# M783new.net
KiCad netlist of a schematic drawn in EAGLE
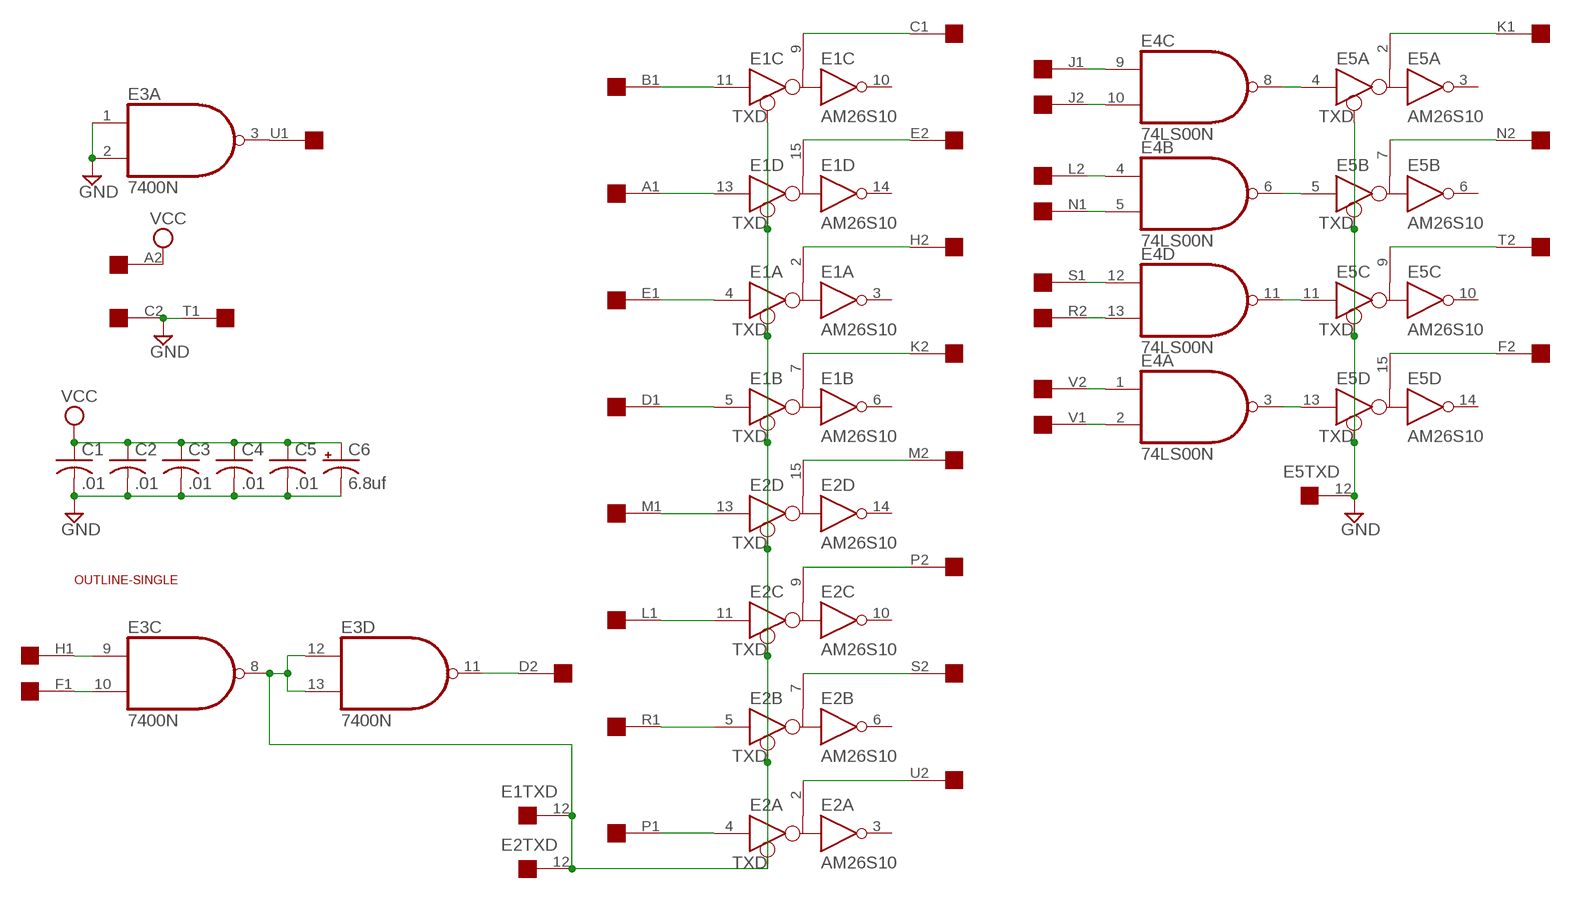
[diagram p0: schematic, sheet 1]

(export (version "E")
  (design (tool "Eeschema 10.0.6"))
  (components
    (comp (ref "C1")
      (value ".01")
      (footprint "eagle-import:C050-025X075")
      (libsource (lib "eagle-import") (part "C-US050-025X075"))
    )
    (comp (ref "C2")
      (value ".01")
      (footprint "eagle-import:C050-025X075")
      (libsource (lib "eagle-import") (part "C-US050-025X075"))
    )
    (comp (ref "C3")
      (value ".01")
      (footprint "eagle-import:C050-025X075")
      (libsource (lib "eagle-import") (part "C-US050-025X075"))
    )
    (comp (ref "C4")
      (value ".01")
      (footprint "eagle-import:C050-025X075")
      (libsource (lib "eagle-import") (part "C-US050-025X075"))
    )
    (comp (ref "C5")
      (value ".01")
      (footprint "eagle-import:C050-025X075")
      (libsource (lib "eagle-import") (part "C-US050-025X075"))
    )
    (comp (ref "C6")
      (value "6.8uf")
      (footprint "eagle-import:E15-5")
      (libsource (lib "eagle-import") (part "CPOL-USE15-5AXIAL"))
    )
    (comp (ref "E1")
      (value "AM26S10")
      (footprint "eagle-import:DIL16")
      (libsource (lib "eagle-import") (part "AM26S10"))
    )
    (comp (ref "E2")
      (value "AM26S10")
      (footprint "eagle-import:DIL16")
      (libsource (lib "eagle-import") (part "AM26S10"))
    )
    (comp (ref "E3")
      (value "7400N")
      (footprint "eagle-import:DIL14")
      (libsource (lib "eagle-import") (part "7400N"))
    )
    (comp (ref "E4")
      (value "74LS00N")
      (footprint "eagle-import:DIL14")
      (libsource (lib "eagle-import") (part "7400NLS"))
    )
    (comp (ref "E5")
      (value "AM26S10")
      (footprint "eagle-import:DIL16")
      (libsource (lib "eagle-import") (part "AM26S10"))
    )
    (comp (ref "U$1")
      (value "SINGLE")
      (footprint "eagle-import:EDGE-CON2")
      (libsource (lib "eagle-import") (part "SINGLE"))
    )
    (comp (ref "U$2")
      (value "OUTLINE-SINGLE")
      (footprint "eagle-import:SINGLE")
      (libsource (lib "eagle-import") (part "OUTLINE-SINGLE"))
    )
  )
  (nets
    (net (code "1") (name "GND") (class "Default")
      (node (ref "C1") (pin "2") (pinfunction "2_2") (pintype "passive"))
      (node (ref "C2") (pin "2") (pinfunction "2_2") (pintype "passive"))
      (node (ref "C3") (pin "2") (pinfunction "2_2") (pintype "passive"))
      (node (ref "C4") (pin "2") (pinfunction "2_2") (pintype "passive"))
      (node (ref "C5") (pin "2") (pinfunction "2_2") (pintype "passive"))
      (node (ref "C6") (pin "-") (pinfunction "-_-") (pintype "passive"))
      (node (ref "E3") (pin "1") (pinfunction "I0_1") (pintype "input"))
      (node (ref "E3") (pin "2") (pinfunction "I1_2") (pintype "input"))
      (node (ref "E5") (pin "12") (pinfunction "TXD_12") (pintype "input"))
      (node (ref "U$1") (pin "C2") (pinfunction "1_C2") (pintype "bidirectional"))
      (node (ref "U$1") (pin "T1") (pinfunction "1_T1") (pintype "bidirectional"))
    )
    (net (code "2") (name "Net-(E1A-B)") (class "Default")
      (node (ref "E1") (pin "2") (pinfunction "B_2") (pintype "bidirectional"))
      (node (ref "U$1") (pin "H2") (pinfunction "1_H2") (pintype "bidirectional"))
    )
    (net (code "3") (name "Net-(E1A-D)") (class "Default")
      (node (ref "E1") (pin "4") (pinfunction "D_4") (pintype "input"))
      (node (ref "U$1") (pin "E1") (pinfunction "1_E1") (pintype "bidirectional"))
    )
    (net (code "4") (name "Net-(E1B-B)") (class "Default")
      (node (ref "E1") (pin "7") (pinfunction "B_7") (pintype "bidirectional"))
      (node (ref "U$1") (pin "K2") (pinfunction "1_K2") (pintype "bidirectional"))
    )
    (net (code "5") (name "Net-(E1B-D)") (class "Default")
      (node (ref "E1") (pin "5") (pinfunction "D_5") (pintype "input"))
      (node (ref "U$1") (pin "D1") (pinfunction "1_D1") (pintype "bidirectional"))
    )
    (net (code "6") (name "Net-(E1C-B)") (class "Default")
      (node (ref "E1") (pin "9") (pinfunction "B_9") (pintype "bidirectional"))
      (node (ref "U$1") (pin "C1") (pinfunction "1_C1") (pintype "bidirectional"))
    )
    (net (code "7") (name "Net-(E1C-D)") (class "Default")
      (node (ref "E1") (pin "11") (pinfunction "D_11") (pintype "input"))
      (node (ref "U$1") (pin "B1") (pinfunction "1_B1") (pintype "bidirectional"))
    )
    (net (code "8") (name "Net-(E1D-B)") (class "Default")
      (node (ref "E1") (pin "15") (pinfunction "B_15") (pintype "bidirectional"))
      (node (ref "U$1") (pin "E2") (pinfunction "1_E2") (pintype "bidirectional"))
    )
    (net (code "9") (name "Net-(E1D-D)") (class "Default")
      (node (ref "E1") (pin "13") (pinfunction "D_13") (pintype "input"))
      (node (ref "U$1") (pin "A1") (pinfunction "1_A1") (pintype "bidirectional"))
    )
    (net (code "10") (name "Net-(E1G-TXD)") (class "Default")
      (node (ref "E1") (pin "12") (pinfunction "TXD_12") (pintype "input"))
      (node (ref "E2") (pin "12") (pinfunction "TXD_12") (pintype "input"))
      (node (ref "E3") (pin "12") (pinfunction "I0_12") (pintype "input"))
      (node (ref "E3") (pin "13") (pinfunction "I1_13") (pintype "input"))
      (node (ref "E3") (pin "8") (pinfunction "O_8") (pintype "output"))
    )
    (net (code "11") (name "Net-(E2A-B)") (class "Default")
      (node (ref "E2") (pin "2") (pinfunction "B_2") (pintype "bidirectional"))
      (node (ref "U$1") (pin "U2") (pinfunction "1_U2") (pintype "bidirectional"))
    )
    (net (code "12") (name "Net-(E2A-D)") (class "Default")
      (node (ref "E2") (pin "4") (pinfunction "D_4") (pintype "input"))
      (node (ref "U$1") (pin "P1") (pinfunction "1_P1") (pintype "bidirectional"))
    )
    (net (code "13") (name "Net-(E2B-B)") (class "Default")
      (node (ref "E2") (pin "7") (pinfunction "B_7") (pintype "bidirectional"))
      (node (ref "U$1") (pin "S2") (pinfunction "1_S2") (pintype "bidirectional"))
    )
    (net (code "14") (name "Net-(E2B-D)") (class "Default")
      (node (ref "E2") (pin "5") (pinfunction "D_5") (pintype "input"))
      (node (ref "U$1") (pin "R1") (pinfunction "1_R1") (pintype "bidirectional"))
    )
    (net (code "15") (name "Net-(E2C-B)") (class "Default")
      (node (ref "E2") (pin "9") (pinfunction "B_9") (pintype "bidirectional"))
      (node (ref "U$1") (pin "P2") (pinfunction "1_P2") (pintype "bidirectional"))
    )
    (net (code "16") (name "Net-(E2C-D)") (class "Default")
      (node (ref "E2") (pin "11") (pinfunction "D_11") (pintype "input"))
      (node (ref "U$1") (pin "L1") (pinfunction "1_L1") (pintype "bidirectional"))
    )
    (net (code "17") (name "Net-(E2D-B)") (class "Default")
      (node (ref "E2") (pin "15") (pinfunction "B_15") (pintype "bidirectional"))
      (node (ref "U$1") (pin "M2") (pinfunction "1_M2") (pintype "bidirectional"))
    )
    (net (code "18") (name "Net-(E2D-D)") (class "Default")
      (node (ref "E2") (pin "13") (pinfunction "D_13") (pintype "input"))
      (node (ref "U$1") (pin "M1") (pinfunction "1_M1") (pintype "bidirectional"))
    )
    (net (code "19") (name "Net-(E3A-O)") (class "Default")
      (node (ref "E3") (pin "3") (pinfunction "O_3") (pintype "output"))
      (node (ref "U$1") (pin "U1") (pinfunction "1_U1") (pintype "bidirectional"))
    )
    (net (code "20") (name "Net-(E3C-I0)") (class "Default")
      (node (ref "E3") (pin "9") (pinfunction "I0_9") (pintype "input"))
      (node (ref "U$1") (pin "H1") (pinfunction "1_H1") (pintype "bidirectional"))
    )
    (net (code "21") (name "Net-(E3C-I1)") (class "Default")
      (node (ref "E3") (pin "10") (pinfunction "I1_10") (pintype "input"))
      (node (ref "U$1") (pin "F1") (pinfunction "1_F1") (pintype "bidirectional"))
    )
    (net (code "22") (name "Net-(E3D-O)") (class "Default")
      (node (ref "E3") (pin "11") (pinfunction "O_11") (pintype "output"))
      (node (ref "U$1") (pin "D2") (pinfunction "1_D2") (pintype "bidirectional"))
    )
    (net (code "23") (name "Net-(E4A-I0)") (class "Default")
      (node (ref "E4") (pin "1") (pinfunction "I0_1") (pintype "input"))
      (node (ref "U$1") (pin "V2") (pinfunction "1_V2") (pintype "bidirectional"))
    )
    (net (code "24") (name "Net-(E4A-I1)") (class "Default")
      (node (ref "E4") (pin "2") (pinfunction "I1_2") (pintype "input"))
      (node (ref "U$1") (pin "V1") (pinfunction "1_V1") (pintype "bidirectional"))
    )
    (net (code "25") (name "Net-(E4A-O)") (class "Default")
      (node (ref "E4") (pin "3") (pinfunction "O_3") (pintype "output"))
      (node (ref "E5") (pin "13") (pinfunction "D_13") (pintype "input"))
    )
    (net (code "26") (name "Net-(E4B-I0)") (class "Default")
      (node (ref "E4") (pin "4") (pinfunction "I0_4") (pintype "input"))
      (node (ref "U$1") (pin "L2") (pinfunction "1_L2") (pintype "bidirectional"))
    )
    (net (code "27") (name "Net-(E4B-I1)") (class "Default")
      (node (ref "E4") (pin "5") (pinfunction "I1_5") (pintype "input"))
      (node (ref "U$1") (pin "N1") (pinfunction "1_N1") (pintype "bidirectional"))
    )
    (net (code "28") (name "Net-(E4B-O)") (class "Default")
      (node (ref "E4") (pin "6") (pinfunction "O_6") (pintype "output"))
      (node (ref "E5") (pin "5") (pinfunction "D_5") (pintype "input"))
    )
    (net (code "29") (name "Net-(E4C-I0)") (class "Default")
      (node (ref "E4") (pin "9") (pinfunction "I0_9") (pintype "input"))
      (node (ref "U$1") (pin "J1") (pinfunction "1_J1") (pintype "bidirectional"))
    )
    (net (code "30") (name "Net-(E4C-I1)") (class "Default")
      (node (ref "E4") (pin "10") (pinfunction "I1_10") (pintype "input"))
      (node (ref "U$1") (pin "J2") (pinfunction "1_J2") (pintype "bidirectional"))
    )
    (net (code "31") (name "Net-(E4C-O)") (class "Default")
      (node (ref "E4") (pin "8") (pinfunction "O_8") (pintype "output"))
      (node (ref "E5") (pin "4") (pinfunction "D_4") (pintype "input"))
    )
    (net (code "32") (name "Net-(E4D-I0)") (class "Default")
      (node (ref "E4") (pin "12") (pinfunction "I0_12") (pintype "input"))
      (node (ref "U$1") (pin "S1") (pinfunction "1_S1") (pintype "bidirectional"))
    )
    (net (code "33") (name "Net-(E4D-I1)") (class "Default")
      (node (ref "E4") (pin "13") (pinfunction "I1_13") (pintype "input"))
      (node (ref "U$1") (pin "R2") (pinfunction "1_R2") (pintype "bidirectional"))
    )
    (net (code "34") (name "Net-(E4D-O)") (class "Default")
      (node (ref "E4") (pin "11") (pinfunction "O_11") (pintype "output"))
      (node (ref "E5") (pin "11") (pinfunction "D_11") (pintype "input"))
    )
    (net (code "35") (name "Net-(E5A-B)") (class "Default")
      (node (ref "E5") (pin "2") (pinfunction "B_2") (pintype "bidirectional"))
      (node (ref "U$1") (pin "K1") (pinfunction "1_K1") (pintype "bidirectional"))
    )
    (net (code "36") (name "Net-(E5B-B)") (class "Default")
      (node (ref "E5") (pin "7") (pinfunction "B_7") (pintype "bidirectional"))
      (node (ref "U$1") (pin "N2") (pinfunction "1_N2") (pintype "bidirectional"))
    )
    (net (code "37") (name "Net-(E5C-B)") (class "Default")
      (node (ref "E5") (pin "9") (pinfunction "B_9") (pintype "bidirectional"))
      (node (ref "U$1") (pin "T2") (pinfunction "1_T2") (pintype "bidirectional"))
    )
    (net (code "38") (name "Net-(E5D-B)") (class "Default")
      (node (ref "E5") (pin "15") (pinfunction "B_15") (pintype "bidirectional"))
      (node (ref "U$1") (pin "F2") (pinfunction "1_F2") (pintype "bidirectional"))
    )
    (net (code "39") (name "VCC") (class "Default")
      (node (ref "C1") (pin "1") (pinfunction "1_1") (pintype "passive"))
      (node (ref "C2") (pin "1") (pinfunction "1_1") (pintype "passive"))
      (node (ref "C3") (pin "1") (pinfunction "1_1") (pintype "passive"))
      (node (ref "C4") (pin "1") (pinfunction "1_1") (pintype "passive"))
      (node (ref "C5") (pin "1") (pinfunction "1_1") (pintype "passive"))
      (node (ref "C6") (pin "+") (pinfunction "+_+") (pintype "passive"))
      (node (ref "U$1") (pin "A2") (pinfunction "1_A2") (pintype "bidirectional"))
    )
    (net (code "40") (name "unconnected-(E1A-R-Pad3)") (class "Default")
      (node (ref "E1") (pin "3") (pinfunction "R_3") (pintype "output"))
    )
    (net (code "41") (name "unconnected-(E1B-R-Pad6)") (class "Default")
      (node (ref "E1") (pin "6") (pinfunction "R_6") (pintype "output"))
    )
    (net (code "42") (name "unconnected-(E1C-R-Pad10)") (class "Default")
      (node (ref "E1") (pin "10") (pinfunction "R_10") (pintype "output"))
    )
    (net (code "43") (name "unconnected-(E1D-R-Pad14)") (class "Default")
      (node (ref "E1") (pin "14") (pinfunction "R_14") (pintype "output"))
    )
    (net (code "44") (name "unconnected-(E2A-R-Pad3)") (class "Default")
      (node (ref "E2") (pin "3") (pinfunction "R_3") (pintype "output"))
    )
    (net (code "45") (name "unconnected-(E2B-R-Pad6)") (class "Default")
      (node (ref "E2") (pin "6") (pinfunction "R_6") (pintype "output"))
    )
    (net (code "46") (name "unconnected-(E2C-R-Pad10)") (class "Default")
      (node (ref "E2") (pin "10") (pinfunction "R_10") (pintype "output"))
    )
    (net (code "47") (name "unconnected-(E2D-R-Pad14)") (class "Default")
      (node (ref "E2") (pin "14") (pinfunction "R_14") (pintype "output"))
    )
    (net (code "48") (name "unconnected-(E5A-R-Pad3)") (class "Default")
      (node (ref "E5") (pin "3") (pinfunction "R_3") (pintype "output"))
    )
    (net (code "49") (name "unconnected-(E5B-R-Pad6)") (class "Default")
      (node (ref "E5") (pin "6") (pinfunction "R_6") (pintype "output"))
    )
    (net (code "50") (name "unconnected-(E5C-R-Pad10)") (class "Default")
      (node (ref "E5") (pin "10") (pinfunction "R_10") (pintype "output"))
    )
    (net (code "51") (name "unconnected-(E5D-R-Pad14)") (class "Default")
      (node (ref "E5") (pin "14") (pinfunction "R_14") (pintype "output"))
    )
  )
)
